# cubex_camera.net
KiCad netlist of a schematic drawn in EAGLE
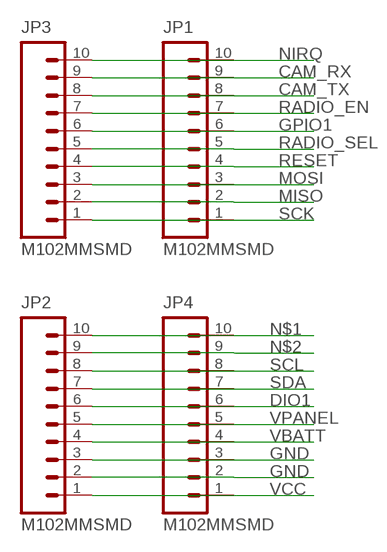
[diagram p0: schematic, sheet 1]

(export (version "E")
  (design (tool "Eeschema 10.0.6"))
  (components
    (comp (ref "JP1")
      (value "M102MMSMD")
      (footprint "eagle-import:1X10-2MM-SMD")
      (libsource (lib "eagle-import") (part "M102MMSMD"))
    )
    (comp (ref "JP2")
      (value "M102MMSMD")
      (footprint "eagle-import:1X10-2MM-SMD")
      (libsource (lib "eagle-import") (part "M102MMSMD"))
    )
    (comp (ref "JP3")
      (value "M102MMSMD")
      (footprint "eagle-import:1X10-2MM-SMD")
      (libsource (lib "eagle-import") (part "M102MMSMD"))
    )
    (comp (ref "JP4")
      (value "M102MMSMD")
      (footprint "eagle-import:1X10-2MM-SMD")
      (libsource (lib "eagle-import") (part "M102MMSMD"))
    )
  )
  (nets
    (net (code "1") (name "/CAM_RX") (class "Default")
      (node (ref "JP1") (pin "9") (pinfunction "9_9") (pintype "passive"))
      (node (ref "JP3") (pin "9") (pinfunction "9_9") (pintype "passive"))
    )
    (net (code "2") (name "/CAM_TX") (class "Default")
      (node (ref "JP1") (pin "8") (pinfunction "8_8") (pintype "passive"))
      (node (ref "JP3") (pin "8") (pinfunction "8_8") (pintype "passive"))
    )
    (net (code "3") (name "/DIO1") (class "Default")
      (node (ref "JP2") (pin "6") (pinfunction "6_6") (pintype "passive"))
      (node (ref "JP4") (pin "6") (pinfunction "6_6") (pintype "passive"))
    )
    (net (code "4") (name "/GND") (class "Default")
      (node (ref "JP2") (pin "2") (pinfunction "2_2") (pintype "passive"))
      (node (ref "JP2") (pin "3") (pinfunction "3_3") (pintype "passive"))
      (node (ref "JP4") (pin "2") (pinfunction "2_2") (pintype "passive"))
      (node (ref "JP4") (pin "3") (pinfunction "3_3") (pintype "passive"))
    )
    (net (code "5") (name "/GPIO1") (class "Default")
      (node (ref "JP1") (pin "6") (pinfunction "6_6") (pintype "passive"))
      (node (ref "JP3") (pin "6") (pinfunction "6_6") (pintype "passive"))
    )
    (net (code "6") (name "/MISO") (class "Default")
      (node (ref "JP1") (pin "2") (pinfunction "2_2") (pintype "passive"))
      (node (ref "JP3") (pin "2") (pinfunction "2_2") (pintype "passive"))
    )
    (net (code "7") (name "/MOSI") (class "Default")
      (node (ref "JP1") (pin "3") (pinfunction "3_3") (pintype "passive"))
      (node (ref "JP3") (pin "3") (pinfunction "3_3") (pintype "passive"))
    )
    (net (code "8") (name "/N$1") (class "Default")
      (node (ref "JP2") (pin "10") (pinfunction "10_10") (pintype "passive"))
      (node (ref "JP4") (pin "10") (pinfunction "10_10") (pintype "passive"))
    )
    (net (code "9") (name "/N$2") (class "Default")
      (node (ref "JP2") (pin "9") (pinfunction "9_9") (pintype "passive"))
      (node (ref "JP4") (pin "9") (pinfunction "9_9") (pintype "passive"))
    )
    (net (code "10") (name "/NIRQ") (class "Default")
      (node (ref "JP1") (pin "10") (pinfunction "10_10") (pintype "passive"))
      (node (ref "JP3") (pin "10") (pinfunction "10_10") (pintype "passive"))
    )
    (net (code "11") (name "/RADIO_EN") (class "Default")
      (node (ref "JP1") (pin "7") (pinfunction "7_7") (pintype "passive"))
      (node (ref "JP3") (pin "7") (pinfunction "7_7") (pintype "passive"))
    )
    (net (code "12") (name "/RADIO_SEL") (class "Default")
      (node (ref "JP1") (pin "5") (pinfunction "5_5") (pintype "passive"))
      (node (ref "JP3") (pin "5") (pinfunction "5_5") (pintype "passive"))
    )
    (net (code "13") (name "/RESET") (class "Default")
      (node (ref "JP1") (pin "4") (pinfunction "4_4") (pintype "passive"))
      (node (ref "JP3") (pin "4") (pinfunction "4_4") (pintype "passive"))
    )
    (net (code "14") (name "/SCK") (class "Default")
      (node (ref "JP1") (pin "1") (pinfunction "1_1") (pintype "passive"))
      (node (ref "JP3") (pin "1") (pinfunction "1_1") (pintype "passive"))
    )
    (net (code "15") (name "/SCL") (class "Default")
      (node (ref "JP2") (pin "8") (pinfunction "8_8") (pintype "passive"))
      (node (ref "JP4") (pin "8") (pinfunction "8_8") (pintype "passive"))
    )
    (net (code "16") (name "/SDA") (class "Default")
      (node (ref "JP2") (pin "7") (pinfunction "7_7") (pintype "passive"))
      (node (ref "JP4") (pin "7") (pinfunction "7_7") (pintype "passive"))
    )
    (net (code "17") (name "/VBATT") (class "Default")
      (node (ref "JP2") (pin "4") (pinfunction "4_4") (pintype "passive"))
      (node (ref "JP4") (pin "4") (pinfunction "4_4") (pintype "passive"))
    )
    (net (code "18") (name "/VCC") (class "Default")
      (node (ref "JP2") (pin "1") (pinfunction "1_1") (pintype "passive"))
      (node (ref "JP4") (pin "1") (pinfunction "1_1") (pintype "passive"))
    )
    (net (code "19") (name "/VPANEL") (class "Default")
      (node (ref "JP2") (pin "5") (pinfunction "5_5") (pintype "passive"))
      (node (ref "JP4") (pin "5") (pinfunction "5_5") (pintype "passive"))
    )
  )
)
